# MUX.net
KiCad netlist of a schematic drawn in Altium Designer
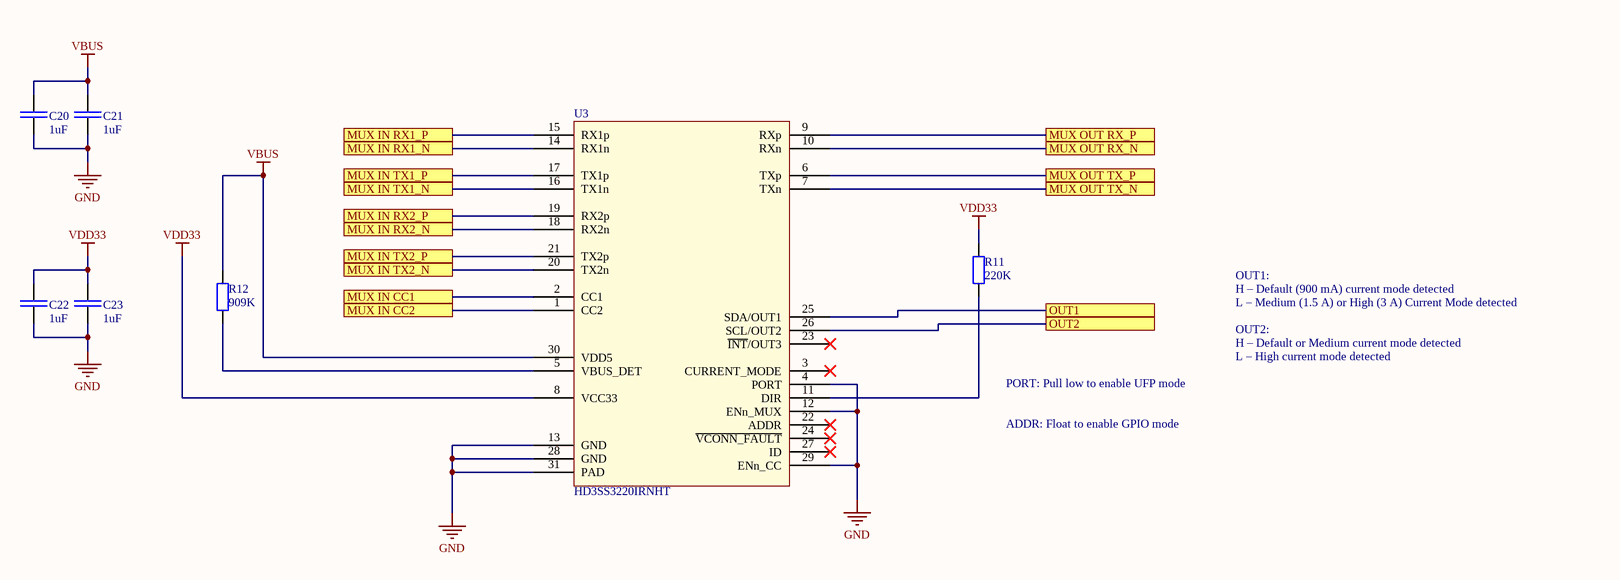
[diagram p0: MUX.SchDoc]

(export (version "E")
  (design (tool "Eeschema 10.0.6"))
  (components
    (comp (ref "C20")
      (value "1uF")
      (footprint "CAP_SM0805_YAGEOCC2_N")
      (description "CAP 1uF SM0805 X7R 25V YAGEO CC2")
      (fields
        (field (name "MANUFACTURER") "Yageo")
        (field (name "MANUFACTURER PART NUMBER") "CC0805KKX7R8BB105")
      )
      (libsource (lib "Yageo") (part "CC0805KKX7R8BB105"))
    )
    (comp (ref "C21")
      (value "1uF")
      (footprint "CAP_SM0805_YAGEOCC2_N")
      (description "CAP 1uF SM0805 X7R 25V YAGEO CC2")
      (fields
        (field (name "MANUFACTURER") "Yageo")
        (field (name "MANUFACTURER PART NUMBER") "CC0805KKX7R8BB105")
      )
      (libsource (lib "Yageo") (part "CC0805KKX7R8BB105"))
    )
    (comp (ref "C22")
      (value "1uF")
      (footprint "CAP_SM0805_YAGEOCC2_N")
      (description "CAP 1uF SM0805 X7R 25V YAGEO CC2")
      (fields
        (field (name "MANUFACTURER") "Yageo")
        (field (name "MANUFACTURER PART NUMBER") "CC0805KKX7R8BB105")
      )
      (libsource (lib "Yageo") (part "CC0805KKX7R8BB105"))
    )
    (comp (ref "C23")
      (value "1uF")
      (footprint "CAP_SM0805_YAGEOCC2_N")
      (description "CAP 1uF SM0805 X7R 25V YAGEO CC2")
      (fields
        (field (name "MANUFACTURER") "Yageo")
        (field (name "MANUFACTURER PART NUMBER") "CC0805KKX7R8BB105")
      )
      (libsource (lib "Yageo") (part "CC0805KKX7R8BB105"))
    )
    (comp (ref "R11")
      (value "220K")
      (footprint "RES_SM0603_YAGEORC_N")
      (description "RES 220K SM0603 YAGEO RC_L")
      (fields
        (field (name "MANUFACTURER") "Yageo")
        (field (name "MANUFACTURER PART NUMBER") "RC0603FR-07220KL")
      )
      (libsource (lib "Integrated_Library_Yageo") (part "RC0603FR-07220KL"))
    )
    (comp (ref "R12")
      (value "909K")
      (footprint "RES_SM0603_YAGEORC_N")
      (description "RES 909K SM0603 YAGEO RC_L")
      (fields
        (field (name "MANUFACTURER") "Yageo")
        (field (name "MANUFACTURER PART NUMBER") "RC0603FR-07909KL")
      )
      (libsource (lib "Yageo") (part "RC0603FR-07909KL"))
    )
    (comp (ref "U3")
      (value "HD3SS3220IRNHT")
      (footprint "QFN40P250X450X80_HS-31N - HD3SS3220IRNHT")
      (description "USB TYPE-C DRP PORT CONTROLLER W")
      (libsource (lib "KBuchka-IntLib") (part "HD3SS3220IRNHT"))
    )
  )
  (nets
    (net (code "1") (name "/MUX IN CC1") (class "Default")
      (node (ref "U3") (pin "2") (pinfunction "CC1_2") (pintype "passive"))
    )
    (net (code "2") (name "/MUX IN CC2") (class "Default")
      (node (ref "U3") (pin "1") (pinfunction "CC2_1") (pintype "passive"))
    )
    (net (code "3") (name "/MUX IN RX1_N") (class "Default")
      (node (ref "U3") (pin "14") (pinfunction "RX1n_14") (pintype "passive"))
    )
    (net (code "4") (name "/MUX IN RX1_P") (class "Default")
      (node (ref "U3") (pin "15") (pinfunction "RX1p_15") (pintype "passive"))
    )
    (net (code "5") (name "/MUX IN RX2_N") (class "Default")
      (node (ref "U3") (pin "18") (pinfunction "RX2n_18") (pintype "passive"))
    )
    (net (code "6") (name "/MUX IN RX2_P") (class "Default")
      (node (ref "U3") (pin "19") (pinfunction "RX2p_19") (pintype "passive"))
    )
    (net (code "7") (name "/MUX IN TX1_N") (class "Default")
      (node (ref "U3") (pin "16") (pinfunction "TX1n_16") (pintype "passive"))
    )
    (net (code "8") (name "/MUX IN TX1_P") (class "Default")
      (node (ref "U3") (pin "17") (pinfunction "TX1p_17") (pintype "passive"))
    )
    (net (code "9") (name "/MUX IN TX2_N") (class "Default")
      (node (ref "U3") (pin "20") (pinfunction "TX2n_20") (pintype "passive"))
    )
    (net (code "10") (name "/MUX IN TX2_P") (class "Default")
      (node (ref "U3") (pin "21") (pinfunction "TX2p_21") (pintype "passive"))
    )
    (net (code "11") (name "/MUX OUT RX_N") (class "Default")
      (node (ref "U3") (pin "10") (pinfunction "RXn_10") (pintype "passive"))
    )
    (net (code "12") (name "/MUX OUT RX_P") (class "Default")
      (node (ref "U3") (pin "9") (pinfunction "RXp_9") (pintype "passive"))
    )
    (net (code "13") (name "/MUX OUT TX_N") (class "Default")
      (node (ref "U3") (pin "7") (pinfunction "TXn_7") (pintype "passive"))
    )
    (net (code "14") (name "/MUX OUT TX_P") (class "Default")
      (node (ref "U3") (pin "6") (pinfunction "TXp_6") (pintype "passive"))
    )
    (net (code "15") (name "/OUT1") (class "Default")
      (node (ref "U3") (pin "25") (pinfunction "SDA/OUT1_25") (pintype "passive"))
    )
    (net (code "16") (name "/OUT2") (class "Default")
      (node (ref "U3") (pin "26") (pinfunction "SCL/OUT2_26") (pintype "passive"))
    )
    (net (code "17") (name "GND") (class "Default")
      (node (ref "C20") (pin "2") (pintype "passive"))
      (node (ref "C21") (pin "2") (pintype "passive"))
      (node (ref "C22") (pin "2") (pintype "passive"))
      (node (ref "C23") (pin "2") (pintype "passive"))
      (node (ref "U3") (pin "12") (pinfunction "ENn_MUX_12") (pintype "passive"))
      (node (ref "U3") (pin "13") (pinfunction "GND_13") (pintype "passive"))
      (node (ref "U3") (pin "28") (pinfunction "GND_28") (pintype "passive"))
      (node (ref "U3") (pin "29") (pinfunction "ENn_CC_29") (pintype "passive"))
      (node (ref "U3") (pin "31") (pinfunction "PAD_31") (pintype "passive"))
      (node (ref "U3") (pin "4") (pinfunction "PORT_4") (pintype "passive"))
    )
    (net (code "18") (name "Net-(U3-DIR)") (class "Default")
      (node (ref "R11") (pin "1") (pintype "passive"))
      (node (ref "U3") (pin "11") (pinfunction "DIR_11") (pintype "passive"))
    )
    (net (code "19") (name "Net-(U3-VBUS_DET)") (class "Default")
      (node (ref "R12") (pin "1") (pintype "passive"))
      (node (ref "U3") (pin "5") (pinfunction "VBUS_DET_5") (pintype "passive"))
    )
    (net (code "20") (name "VBUS") (class "Default")
      (node (ref "C20") (pin "1") (pintype "passive"))
      (node (ref "C21") (pin "1") (pintype "passive"))
      (node (ref "R12") (pin "2") (pintype "passive"))
      (node (ref "U3") (pin "30") (pinfunction "VDD5_30") (pintype "passive"))
    )
    (net (code "21") (name "VDD33") (class "Default")
      (node (ref "C22") (pin "1") (pintype "passive"))
      (node (ref "C23") (pin "1") (pintype "passive"))
      (node (ref "R11") (pin "2") (pintype "passive"))
      (node (ref "U3") (pin "8") (pinfunction "VCC33_8") (pintype "passive"))
    )
    (net (code "22") (name "unconnected-(U3-ADDR-Pad22)") (class "Default")
      (node (ref "U3") (pin "22") (pinfunction "ADDR_22") (pintype "passive+no_connect"))
    )
    (net (code "23") (name "unconnected-(U3-CURRENT_MODE-Pad3)") (class "Default")
      (node (ref "U3") (pin "3") (pinfunction "CURRENT_MODE_3") (pintype "passive+no_connect"))
    )
    (net (code "24") (name "unconnected-(U3-ID-Pad27)") (class "Default")
      (node (ref "U3") (pin "27") (pinfunction "ID_27") (pintype "passive+no_connect"))
    )
    (net (code "25") (name "unconnected-(U3-~{INT}{slash}OUT3-Pad23)") (class "Default")
      (node (ref "U3") (pin "23") (pinfunction "~{INT}/OUT3_23") (pintype "passive+no_connect"))
    )
    (net (code "26") (name "unconnected-(U3-~{VCONN_FAULT}-Pad24)") (class "Default")
      (node (ref "U3") (pin "24") (pinfunction "~{VCONN_FAULT}_24") (pintype "passive+no_connect"))
    )
  )
)
